# Skematik_Grader-GPS_-_v1.net
KiCad netlist of a schematic drawn in Altium Designer
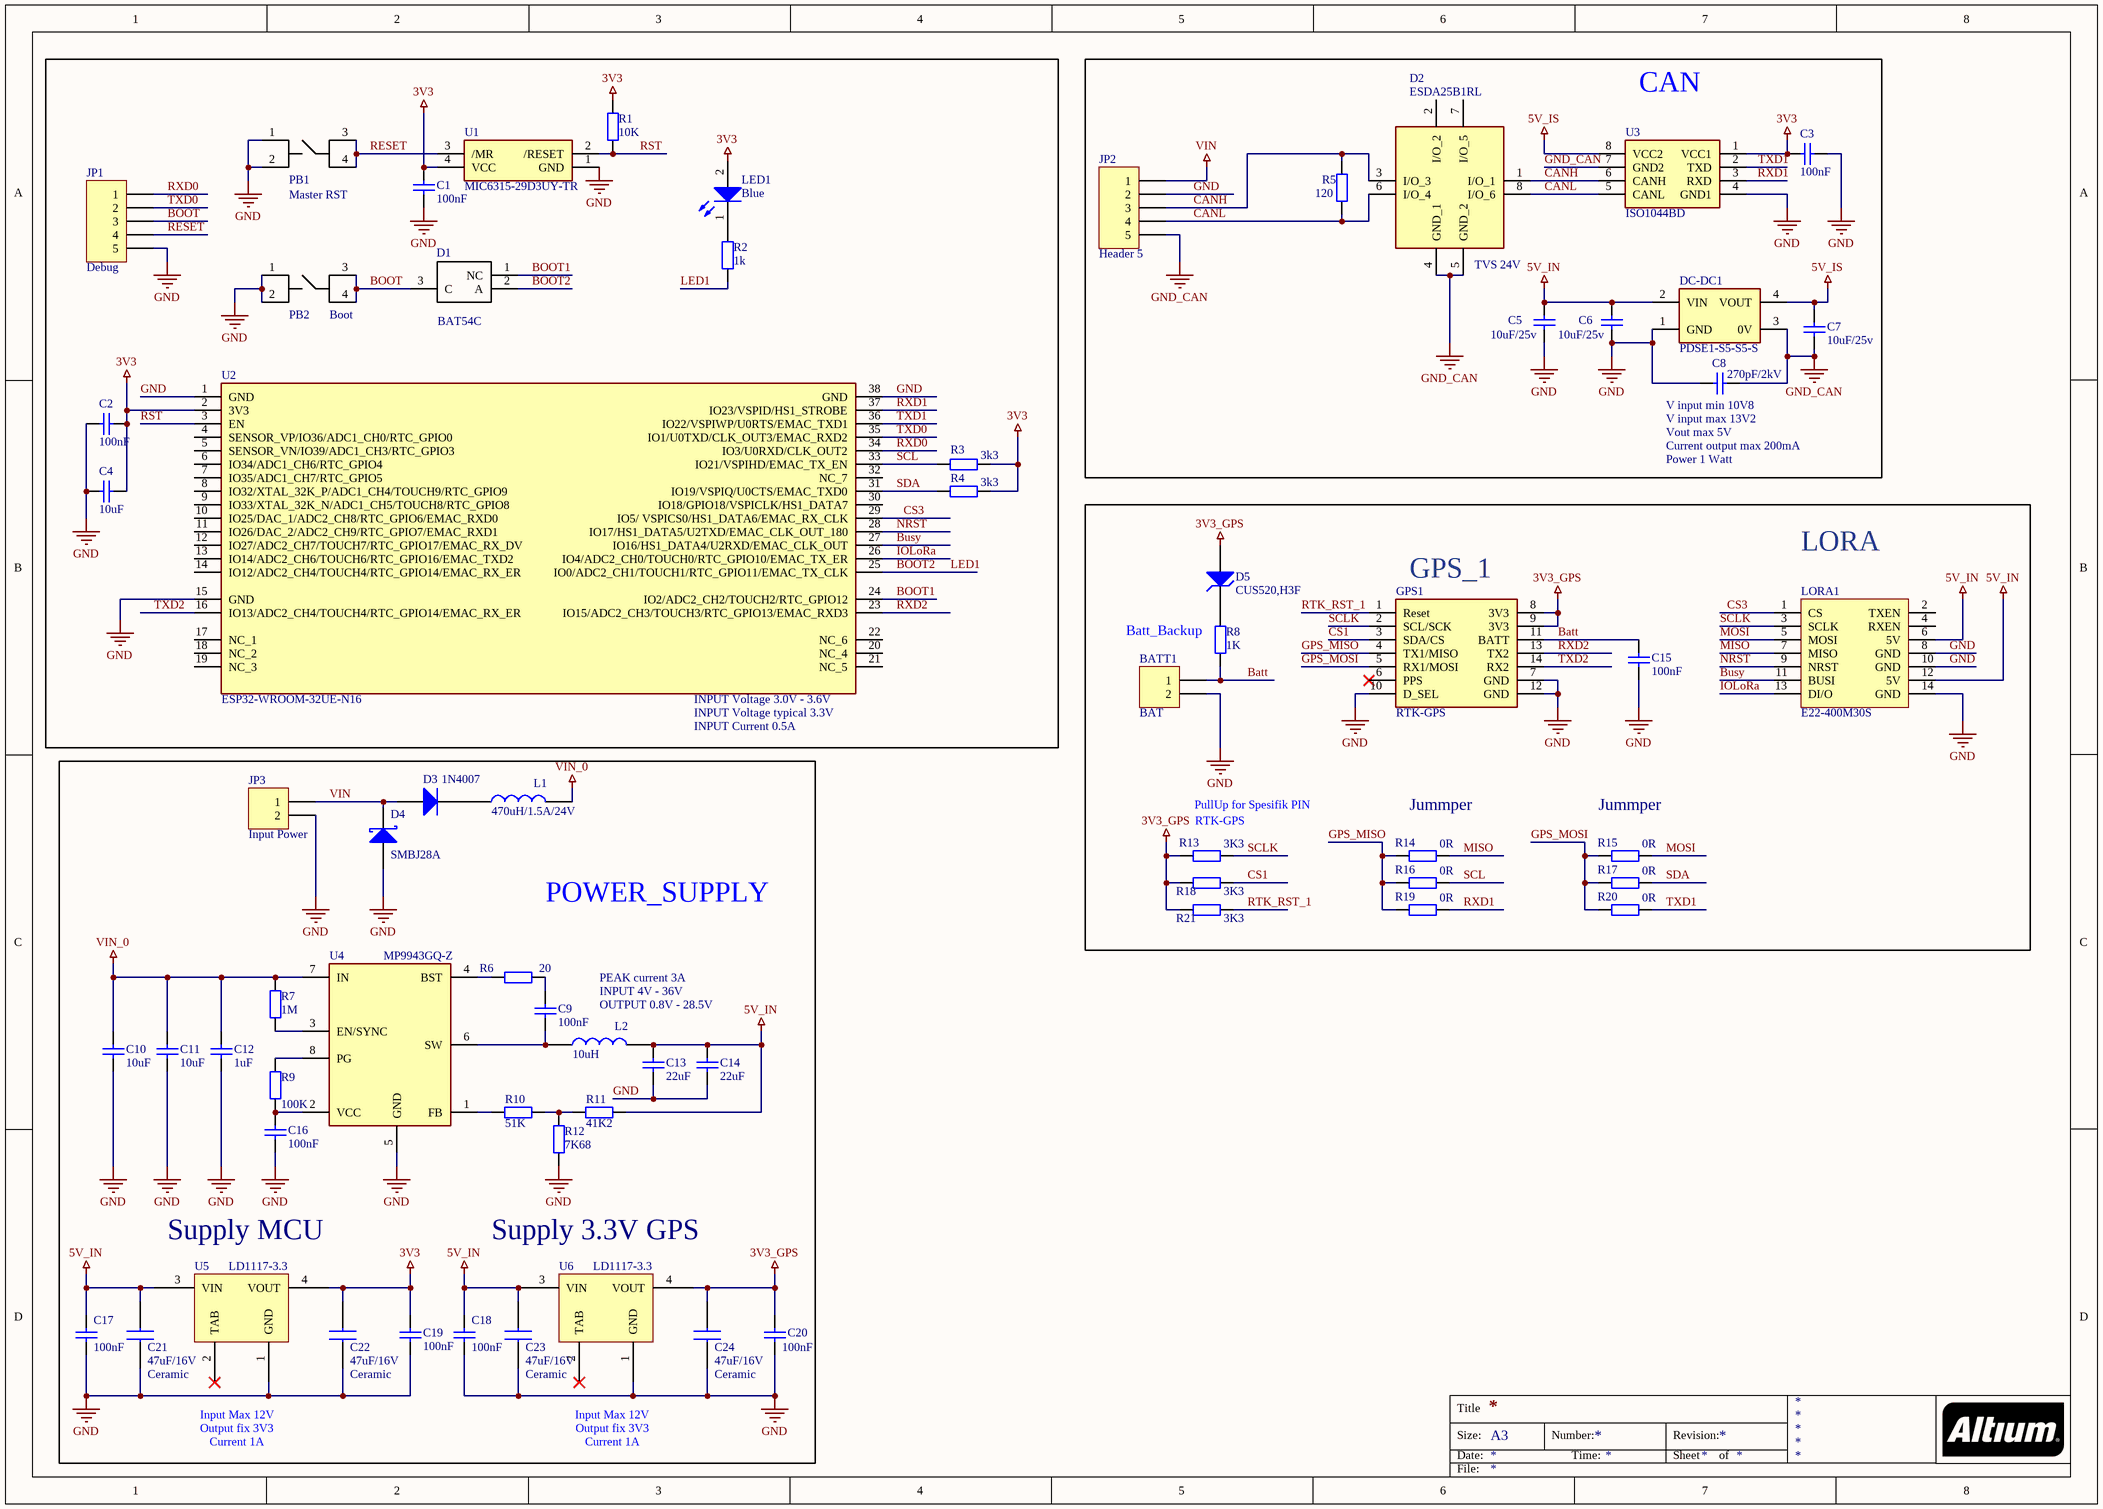
[diagram p0: Skematik_Grader-GPS - v1.SchDoc]

(export (version "E")
  (design (tool "Eeschema 10.0.6"))
  (components
    (comp (ref "BATT1")
      (value "BAT")
      (footprint "CR1220")
      (description "Header, 2-Pin")
      (fields (field (name "PUBLISHER") "Altium Limited"))
      (libsource (lib "Miscellaneous Connectors") (part "MHDR1X2"))
    )
    (comp (ref "C1")
      (value "100nF")
      (footprint "CAPC2012X135N")
      (description "Capacitor")
      (fields (field (name "PUBLISHER") "Altium Limited"))
      (libsource (lib "Miscellaneous Devices") (part "Cap"))
    )
    (comp (ref "C2")
      (value "100nF")
      (footprint "CAPC2012X135N")
      (description "Capacitor")
      (fields (field (name "PUBLISHER") "Altium Limited"))
      (libsource (lib "Miscellaneous Devices") (part "Cap"))
    )
    (comp (ref "C3")
      (value "100nF")
      (footprint "CAPC2012X135N")
      (description "Capacitor")
      (fields (field (name "PUBLISHER") "Altium Limited"))
      (libsource (lib "Miscellaneous Devices") (part "Cap"))
    )
    (comp (ref "C4")
      (value "10uF")
      (footprint "CAPC3216X100N")
      (description "Capacitor")
      (fields (field (name "PUBLISHER") "Altium Limited"))
      (libsource (lib "Miscellaneous Devices") (part "Cap"))
    )
    (comp (ref "C5")
      (value "10uF/25v")
      (footprint "CAPC3216X180N")
      (description "Capacitor")
      (fields (field (name "Comment") "10uF") (field (name "PUBLISHER") "Altium Limited"))
      (libsource (lib "Miscellaneous Devices") (part "Cap"))
    )
    (comp (ref "C6")
      (value "10uF/25v")
      (footprint "CAPC3216X180N")
      (description "Capacitor")
      (fields (field (name "Comment") "10uF") (field (name "PUBLISHER") "Altium Limited"))
      (libsource (lib "Miscellaneous Devices") (part "Cap"))
    )
    (comp (ref "C7")
      (value "10uF/25v")
      (footprint "CAPC3216X100N")
      (description "Capacitor")
      (fields (field (name "Comment") "2.2uF/25V") (field (name "PUBLISHER") "Altium Limited"))
      (libsource (lib "Miscellaneous Devices") (part "Cap"))
    )
    (comp (ref "C8")
      (value "270pF/2kV")
      (footprint "CAPC3216X175N")
      (description "Capacitor")
      (fields (field (name "PUBLISHER") "Altium Limited"))
      (libsource (lib "Miscellaneous Devices") (part "Cap"))
    )
    (comp (ref "C9")
      (value "100nF")
      (footprint "CAPC2012X135N")
      (description "Capacitor")
      (fields (field (name "PUBLISHER") "Altium Limited"))
      (libsource (lib "Miscellaneous Devices") (part "Cap"))
    )
    (comp (ref "C10")
      (value "10uF")
      (footprint "CAPC3216X180N")
      (description "Capacitor")
      (fields (field (name "PUBLISHER") "Altium Limited"))
      (libsource (lib "Miscellaneous Devices") (part "Cap"))
    )
    (comp (ref "C11")
      (value "10uF")
      (footprint "CAPC3216X180N")
      (description "Capacitor")
      (fields (field (name "PUBLISHER") "Altium Limited"))
      (libsource (lib "Miscellaneous Devices") (part "Cap"))
    )
    (comp (ref "C12")
      (value "1uF")
      (footprint "CAPC2012X135N")
      (description "Capacitor")
      (fields (field (name "PUBLISHER") "Altium Limited"))
      (libsource (lib "Miscellaneous Devices") (part "Cap"))
    )
    (comp (ref "C13")
      (value "22uF")
      (footprint "CAPC3216X180N")
      (description "Capacitor")
      (fields (field (name "PUBLISHER") "Altium Limited"))
      (libsource (lib "Miscellaneous Devices") (part "Cap"))
    )
    (comp (ref "C14")
      (value "22uF")
      (footprint "CAPC3216X180N")
      (description "Capacitor")
      (fields (field (name "PUBLISHER") "Altium Limited"))
      (libsource (lib "Miscellaneous Devices") (part "Cap"))
    )
    (comp (ref "C15")
      (value "100nF")
      (footprint "CAPC2012X135N")
      (description "Capacitor")
      (fields (field (name "PUBLISHER") "Altium Limited"))
      (libsource (lib "Miscellaneous Devices") (part "Cap"))
    )
    (comp (ref "C16")
      (value "100nF")
      (footprint "CAPC2012X135N")
      (description "Capacitor")
      (fields (field (name "PUBLISHER") "Altium Limited"))
      (libsource (lib "Miscellaneous Devices") (part "Cap"))
    )
    (comp (ref "C17")
      (value "100nF")
      (footprint "CAPC2012X135N")
      (description "Capacitor")
      (fields (field (name "PUBLISHER") "Altium Limited"))
      (libsource (lib "Miscellaneous Devices") (part "Cap"))
    )
    (comp (ref "C18")
      (value "100nF")
      (footprint "CAPC2012X135N")
      (description "Capacitor")
      (fields (field (name "PUBLISHER") "Altium Limited"))
      (libsource (lib "Miscellaneous Devices") (part "Cap"))
    )
    (comp (ref "C19")
      (value "100nF")
      (footprint "CAPC2012X135N")
      (description "Capacitor")
      (fields (field (name "PUBLISHER") "Altium Limited"))
      (libsource (lib "Miscellaneous Devices") (part "Cap"))
    )
    (comp (ref "C20")
      (value "100nF")
      (footprint "CAPC2012X135N")
      (description "Capacitor")
      (fields (field (name "PUBLISHER") "Altium Limited"))
      (libsource (lib "Miscellaneous Devices") (part "Cap"))
    )
    (comp (ref "C21")
      (value "47uF/16V")
      (footprint "CAPC3225X220N")
      (description "Capacitor")
      (fields
        (field (name "MANUFACTURER_PART_NUMBER") "KCM55WC71E107MH13L")
        (field (name "MOUSER PART NUMBER") "81-KCM55WC71E107MH13")
        (field (name "TYPE") "Ceramic")
      )
      (libsource (lib "*") (part "KCM55WC71E107MH13L"))
    )
    (comp (ref "C22")
      (value "47uF/16V")
      (footprint "CAPC3225X220N")
      (description "Capacitor")
      (fields
        (field (name "MANUFACTURER_PART_NUMBER") "KCM55WC71E107MH13L")
        (field (name "MOUSER PART NUMBER") "81-KCM55WC71E107MH13")
        (field (name "TYPE") "Ceramic")
      )
      (libsource (lib "*") (part "KCM55WC71E107MH13L"))
    )
    (comp (ref "C23")
      (value "47uF/16V")
      (footprint "CAPC3225X220N")
      (description "Capacitor")
      (fields
        (field (name "MANUFACTURER_PART_NUMBER") "KCM55WC71E107MH13L")
        (field (name "MOUSER PART NUMBER") "81-KCM55WC71E107MH13")
        (field (name "TYPE") "Ceramic")
      )
      (libsource (lib "*") (part "KCM55WC71E107MH13L"))
    )
    (comp (ref "C24")
      (value "47uF/16V")
      (footprint "CAPC3225X220N")
      (description "Capacitor")
      (fields
        (field (name "MANUFACTURER_PART_NUMBER") "KCM55WC71E107MH13L")
        (field (name "MOUSER PART NUMBER") "81-KCM55WC71E107MH13")
        (field (name "TYPE") "Ceramic")
      )
      (libsource (lib "*") (part "KCM55WC71E107MH13L"))
    )
    (comp (ref "D1") (value "BAT54C") (footprint "SC59-3") (libsource (lib "Sigit") (part "RB420")))
    (comp (ref "D2")
      (value "ESDA25B1RL")
      (footprint "SOIC127P600X175-8AN")
      (description "TVS DIODA")
      (fields (field (name "MOUSER PART NUMBER") "511-ESDA25B1-TR"))
      (libsource (lib "bayu") (part "ESDA25B1RL"))
    )
    (comp (ref "D3")
      (value "1N4007")
      (footprint "DO-214AC")
      (description "1 Amp General Purpose Rectifier")
      (fields (field (name "PUBLISHER") "Altium Limited"))
      (libsource (lib "Miscellaneous Devices") (part "Diode 1N4001"))
    )
    (comp (ref "D4")
      (value "SMBJ28A")
      (footprint "PBL - SMD Packages:DO-214AA")
      (description "Schottky Diode")
      (fields (field (name "PUBLISHER") "Altium Limited"))
      (libsource (lib "Miscellaneous Devices") (part "D Schottky"))
    )
    (comp (ref "D5")
      (value "CUS520,H3F")
      (footprint "SOD323")
      (description "Zener Diode")
      (fields (field (name "PUBLISHER") "Altium Limited"))
      (libsource (lib "Miscellaneous Devices") (part "D Zener"))
    )
    (comp (ref "DC-DC1")
      (value "PDSE1-S5-S5-S")
      (footprint "DC-DC")
      (description "DC-DC 24 to 12 \r\nPDSE1-S24-S12-S")
      (libsource (lib "rapp") (part "PDSE1-S24-S12-S"))
    )
    (comp (ref "GPS1")
      (value "RTK-GPS")
      (footprint "ZED-F9P")
      (description "GPS Sensor")
      (libsource (lib "rapp") (part "ZED-F9P"))
    )
    (comp (ref "JP1")
      (value "Debug")
      (footprint "HDR1X5")
      (description "Header, 5-Pin")
      (fields (field (name "PUBLISHER") "Altium Limited"))
      (libsource (lib "Miscellaneous Connectors") (part "Header 5"))
    )
    (comp (ref "JP2")
      (value "Header 5")
      (footprint "Term_Block - 5P")
      (description "Header, 5-Pin")
      (fields (field (name "PUBLISHER") "Altium Limited"))
      (libsource (lib "Miscellaneous Connectors") (part "Header 5"))
    )
    (comp (ref "JP3")
      (value "Input Power")
      (footprint "HDR1X2")
      (description "Header, 2-Pin")
      (fields (field (name "PUBLISHER") "Altium Limited"))
      (libsource (lib "Miscellaneous Connectors") (part "Header 2"))
    )
    (comp (ref "L1")
      (value "470uH/1.5A/24V")
      (footprint "INDP9630X28N")
      (description "Inductor")
      (fields
        (field (name "MANUFACTURER_PART_NUMBER") "MPL-AL5050-100")
        (field (name "MOUSER PART NUMBER") "946-MPL-AL5050-100")
      )
      (libsource (lib "*") (part "MPL-AL5050-100"))
    )
    (comp (ref "L2")
      (value "10uH")
      (footprint "IND_5.4x5.3")
      (description "Inductor")
      (fields
        (field (name "MANUFACTURER_PART_NUMBER") "MPL-AL5050-100")
        (field (name "MOUSER PART NUMBER") "946-MPL-AL5050-100")
      )
      (libsource (lib "*") (part "MPL-AL5050-100"))
    )
    (comp (ref "LED1")
      (value "Blue")
      (footprint "LED-0805-A")
      (description "Typical Blue GaAs LED")
      (fields (field (name "PUBLISHER") "Altium Limited"))
      (libsource (lib "Miscellaneous Devices") (part "LED1"))
    )
    (comp (ref "LORA1")
      (value "E22-400M30S")
      (footprint "22s-V3")
      (description "Lora 22S / Lora 30S")
      (libsource (lib "rapp") (part "Lora"))
    )
    (comp (ref "PB1")
      (value "Master RST")
      (footprint "PushButton1688")
      (libsource (lib "Sigit") (part "PB_SW_1"))
    )
    (comp (ref "PB2") (value "Boot") (footprint "PushButton1688") (libsource (lib "Sigit") (part "PB_SW_1")))
    (comp (ref "R1")
      (value "10K")
      (footprint "RESC2012X70N")
      (description "Resistor")
      (fields (field (name "PUBLISHER") "Altium Limited"))
      (libsource (lib "Miscellaneous Devices") (part "Res2"))
    )
    (comp (ref "R2")
      (value "1k")
      (footprint "RESC2012X70N")
      (description "Resistor")
      (fields (field (name "PUBLISHER") "Altium Limited"))
      (libsource (lib "Miscellaneous Devices") (part "Res2"))
    )
    (comp (ref "R3")
      (value "3k3")
      (footprint "RESC2012X70N")
      (description "Resistor")
      (fields (field (name "PUBLISHER") "Altium Limited"))
      (libsource (lib "Miscellaneous Devices") (part "Res2"))
    )
    (comp (ref "R4")
      (value "3k3")
      (footprint "RESC2012X70N")
      (description "Resistor")
      (fields (field (name "PUBLISHER") "Altium Limited"))
      (libsource (lib "Miscellaneous Devices") (part "Res2"))
    )
    (comp (ref "R5")
      (value "120")
      (footprint "RESC2012X70N")
      (description "Resistor")
      (fields (field (name "PUBLISHER") "Altium Limited"))
      (libsource (lib "") (part "Res2_1"))
    )
    (comp (ref "R6")
      (value "20")
      (footprint "RESC2012X70N")
      (description "Resistor")
      (fields (field (name "PUBLISHER") "Altium Limited"))
      (libsource (lib "") (part "Res2_1"))
    )
    (comp (ref "R7")
      (value "1M")
      (footprint "RESC2012X70N")
      (description "Resistor")
      (fields (field (name "PUBLISHER") "Altium Limited"))
      (libsource (lib "") (part "Res2_2"))
    )
    (comp (ref "R8")
      (value "1K")
      (footprint "RESC2012X70N")
      (description "Resistor")
      (fields (field (name "PUBLISHER") "Altium Limited"))
      (libsource (lib "") (part "Res2_3"))
    )
    (comp (ref "R9")
      (value "100K")
      (footprint "RESC2012X70N")
      (description "Resistor")
      (fields (field (name "PUBLISHER") "Altium Limited"))
      (libsource (lib "") (part "Res2_2"))
    )
    (comp (ref "R10")
      (value "51K")
      (footprint "RESC2012X70N")
      (description "Resistor")
      (fields (field (name "PUBLISHER") "Altium Limited"))
      (libsource (lib "") (part "Res2_1"))
    )
    (comp (ref "R11")
      (value "41K2")
      (footprint "RESC2012X70N")
      (description "Resistor")
      (fields (field (name "PUBLISHER") "Altium Limited"))
      (libsource (lib "") (part "Res2_1"))
    )
    (comp (ref "R12")
      (value "7K68")
      (footprint "RESC2012X70N")
      (description "Resistor")
      (fields (field (name "PUBLISHER") "Altium Limited"))
      (libsource (lib "Miscellaneous Devices") (part "Res2"))
    )
    (comp (ref "R13")
      (value "3K3")
      (footprint "RESC2012X70N")
      (description "Resistor")
      (fields (field (name "PUBLISHER") "Altium Limited"))
      (libsource (lib "") (part "Res2_2"))
    )
    (comp (ref "R14")
      (value "0R")
      (footprint "RESC2012X70N")
      (description "Resistor")
      (fields (field (name "PUBLISHER") "Altium Limited"))
      (libsource (lib "") (part "Res2_2"))
    )
    (comp (ref "R15")
      (value "0R")
      (footprint "RESC2012X70N")
      (description "Resistor")
      (fields (field (name "PUBLISHER") "Altium Limited"))
      (libsource (lib "") (part "Res2_2"))
    )
    (comp (ref "R16")
      (value "0R")
      (footprint "RESC2012X70N")
      (description "Resistor")
      (fields (field (name "PUBLISHER") "Altium Limited"))
      (libsource (lib "") (part "Res2_2"))
    )
    (comp (ref "R17")
      (value "0R")
      (footprint "RESC2012X70N")
      (description "Resistor")
      (fields (field (name "PUBLISHER") "Altium Limited"))
      (libsource (lib "") (part "Res2_2"))
    )
    (comp (ref "R18")
      (value "3K3")
      (footprint "RESC2012X70N")
      (description "Resistor")
      (fields (field (name "PUBLISHER") "Altium Limited"))
      (libsource (lib "Miscellaneous Devices") (part "Res2"))
    )
    (comp (ref "R19")
      (value "0R")
      (footprint "RESC2012X70N")
      (description "Resistor")
      (fields (field (name "PUBLISHER") "Altium Limited"))
      (libsource (lib "") (part "Res2_2"))
    )
    (comp (ref "R20")
      (value "0R")
      (footprint "RESC2012X70N")
      (description "Resistor")
      (fields (field (name "PUBLISHER") "Altium Limited"))
      (libsource (lib "") (part "Res2_2"))
    )
    (comp (ref "R21")
      (value "3K3")
      (footprint "RESC2012X70N")
      (description "Resistor")
      (fields (field (name "PUBLISHER") "Altium Limited"))
      (libsource (lib "Miscellaneous Devices") (part "Res2"))
    )
    (comp (ref "U1")
      (value "MIC6315-29D3UY-TR")
      (footprint "MIC631529D3UYTR")
      (description "Integrated Circuit")
      (fields (field (name "MOUSER PART NUMBER") "998-MIC6315-29D3UYTR"))
      (libsource (lib "*") (part "MIC6315-29D3UY-TR"))
    )
    (comp (ref "U2")
      (value "ESP32-WROOM-32UE-N16")
      (footprint "ESP32WROOM32UEN16")
      (libsource (lib "rapp") (part "ESP32-WROOM-32UE-N16A"))
    )
    (comp (ref "U3")
      (value "ISO1044BD")
      (footprint "SOIC127P600X175-8AN")
      (description "Integrated Circuit")
      (fields (field (name "MOUSER PART NUMBER") "595-ISO1044BD"))
      (libsource (lib "*") (part "ISO1044BD"))
    )
    (comp (ref "U4")
      (value "MP9943GQ-Z")
      (footprint "MP9943GQz-smd")
      (description "Integrated Circuit")
      (fields (field (name "MOUSER PART NUMBER") "946-MP9943GQ-Z"))
      (libsource (lib "bayu") (part "MP9943GQ-Z"))
    )
    (comp (ref "U5")
      (value "LD1117-3.3")
      (footprint "PBL - SMD Packages:TO-252")
      (description "AP2114D-3.3TRG1, 3.3V LDO Voltage Regulator")
      (libsource (lib "Sigit") (part "LM1117-3.3V"))
    )
    (comp (ref "U6")
      (value "LD1117-3.3")
      (footprint "PBL - SMD Packages:TO-252")
      (description "AP2114D-3.3TRG1, 3.3V LDO Voltage Regulator")
      (libsource (lib "Sigit") (part "LM1117-3.3V"))
    )
  )
  (nets
    (net (code "1") (name "/BOOT") (class "Default")
      (node (ref "D1") (pin "3") (pinfunction "C_3") (pintype "passive"))
      (node (ref "JP1") (pin "3") (pinfunction "3_3") (pintype "passive"))
      (node (ref "PB2") (pin "3") (pinfunction "3_3") (pintype "passive"))
      (node (ref "PB2") (pin "4") (pinfunction "4_4") (pintype "passive"))
    )
    (net (code "2") (name "/BOOT1") (class "Default")
      (node (ref "D1") (pin "1") (pinfunction "NC_1") (pintype "passive"))
      (node (ref "U2") (pin "24") (pinfunction "IO2/ADC2_CH2/TOUCH2/RTC_GPIO12_24") (pintype "passive"))
    )
    (net (code "3") (name "/BOOT2") (class "Default")
      (node (ref "D1") (pin "2") (pinfunction "A_2") (pintype "passive"))
      (node (ref "R2") (pin "2") (pinfunction "2_2") (pintype "passive"))
      (node (ref "U2") (pin "25") (pinfunction "IO0/ADC2_CH1/TOUCH1/RTC_GPIO11/EMAC_TX_CLK_25") (pintype "passive"))
    )
    (net (code "4") (name "/Batt") (class "Default")
      (node (ref "BATT1") (pin "1") (pinfunction "1_1") (pintype "passive"))
      (node (ref "C15") (pin "2") (pinfunction "2_2") (pintype "passive"))
      (node (ref "GPS1") (pin "11") (pinfunction "BATT_11") (pintype "passive"))
      (node (ref "R8") (pin "1") (pinfunction "1_1") (pintype "passive"))
    )
    (net (code "5") (name "/Busy") (class "Default")
      (node (ref "LORA1") (pin "11") (pinfunction "BUSI_11") (pintype "passive"))
      (node (ref "U2") (pin "27") (pinfunction "IO16/HS1_DATA4/U2RXD/EMAC_CLK_OUT_27") (pintype "passive"))
    )
    (net (code "6") (name "/CANH") (class "Default")
      (node (ref "D2") (pin "1") (pinfunction "I/O_1_1") (pintype "passive"))
      (node (ref "D2") (pin "3") (pinfunction "I/O_3_3") (pintype "passive"))
      (node (ref "JP2") (pin "3") (pinfunction "3_3") (pintype "passive"))
      (node (ref "R5") (pin "1") (pinfunction "1_1") (pintype "passive"))
      (node (ref "U3") (pin "6") (pinfunction "CANH_6") (pintype "passive"))
    )
    (net (code "7") (name "/CANL") (class "Default")
      (node (ref "D2") (pin "6") (pinfunction "I/O_4_6") (pintype "passive"))
      (node (ref "D2") (pin "8") (pinfunction "I/O_6_8") (pintype "passive"))
      (node (ref "JP2") (pin "4") (pinfunction "4_4") (pintype "passive"))
      (node (ref "R5") (pin "2") (pinfunction "2_2") (pintype "passive"))
      (node (ref "U3") (pin "5") (pinfunction "CANL_5") (pintype "passive"))
    )
    (net (code "8") (name "/CS1") (class "Default")
      (node (ref "GPS1") (pin "3") (pinfunction "SDA/CS_3") (pintype "passive"))
      (node (ref "R18") (pin "1") (pinfunction "1_1") (pintype "passive"))
    )
    (net (code "9") (name "/CS3") (class "Default")
      (node (ref "LORA1") (pin "1") (pinfunction "CS_1") (pintype "passive"))
      (node (ref "U2") (pin "29") (pinfunction "IO5/_VSPICS0/HS1_DATA6/EMAC_RX_CLK_29") (pintype "passive"))
    )
    (net (code "10") (name "/GPS_MISO") (class "Default")
      (node (ref "GPS1") (pin "4") (pinfunction "TX1/MISO_4") (pintype "passive"))
      (node (ref "R14") (pin "1") (pinfunction "1_1") (pintype "passive"))
      (node (ref "R16") (pin "1") (pinfunction "1_1") (pintype "passive"))
      (node (ref "R19") (pin "1") (pinfunction "1_1") (pintype "passive"))
    )
    (net (code "11") (name "/GPS_MOSI") (class "Default")
      (node (ref "GPS1") (pin "5") (pinfunction "RX1/MOSI_5") (pintype "passive"))
      (node (ref "R15") (pin "1") (pinfunction "1_1") (pintype "passive"))
      (node (ref "R17") (pin "1") (pinfunction "1_1") (pintype "passive"))
      (node (ref "R20") (pin "1") (pinfunction "1_1") (pintype "passive"))
    )
    (net (code "12") (name "/IOLoRa") (class "Default")
      (node (ref "LORA1") (pin "13") (pinfunction "DI/O_13") (pintype "passive"))
      (node (ref "U2") (pin "26") (pinfunction "IO4/ADC2_CH0/TOUCH0/RTC_GPIO10/EMAC_TX_ER_26") (pintype "passive"))
    )
    (net (code "13") (name "/MISO") (class "Default")
      (node (ref "LORA1") (pin "7") (pinfunction "MISO_7") (pintype "passive"))
      (node (ref "R14") (pin "2") (pinfunction "2_2") (pintype "passive"))
    )
    (net (code "14") (name "/MOSI") (class "Default")
      (node (ref "LORA1") (pin "5") (pinfunction "MOSI_5") (pintype "passive"))
      (node (ref "R15") (pin "2") (pinfunction "2_2") (pintype "passive"))
    )
    (net (code "15") (name "/NRST") (class "Default")
      (node (ref "LORA1") (pin "9") (pinfunction "NRST_9") (pintype "passive"))
      (node (ref "U2") (pin "28") (pinfunction "IO17/HS1_DATA5/U2TXD/EMAC_CLK_OUT_180_28") (pintype "passive"))
    )
    (net (code "16") (name "/RESET") (class "Default")
      (node (ref "JP1") (pin "4") (pinfunction "4_4") (pintype "passive"))
      (node (ref "PB1") (pin "3") (pinfunction "3_3") (pintype "passive"))
      (node (ref "PB1") (pin "4") (pinfunction "4_4") (pintype "passive"))
      (node (ref "U1") (pin "3") (pinfunction "/MR_3") (pintype "passive"))
    )
    (net (code "17") (name "/RST") (class "Default")
      (node (ref "R1") (pin "2") (pinfunction "2_2") (pintype "passive"))
      (node (ref "U1") (pin "2") (pinfunction "/RESET_2") (pintype "passive"))
      (node (ref "U2") (pin "3") (pinfunction "EN_3") (pintype "passive"))
    )
    (net (code "18") (name "/RTK_RST_1") (class "Default")
      (node (ref "GPS1") (pin "1") (pinfunction "Reset_1") (pintype "passive"))
      (node (ref "R21") (pin "1") (pinfunction "1_1") (pintype "passive"))
    )
    (net (code "19") (name "/RXD0") (class "Default")
      (node (ref "JP1") (pin "1") (pinfunction "1_1") (pintype "passive"))
      (node (ref "U2") (pin "34") (pinfunction "IO3/U0RXD/CLK_OUT2_34") (pintype "passive"))
    )
    (net (code "20") (name "/RXD1") (class "Default")
      (node (ref "R19") (pin "2") (pinfunction "2_2") (pintype "passive"))
      (node (ref "U2") (pin "37") (pinfunction "IO23/VSPID/HS1_STROBE_37") (pintype "passive"))
      (node (ref "U3") (pin "3") (pinfunction "RXD_3") (pintype "passive"))
    )
    (net (code "21") (name "/RXD2") (class "Default")
      (node (ref "GPS1") (pin "13") (pinfunction "TX2_13") (pintype "passive"))
      (node (ref "U2") (pin "23") (pinfunction "IO15/ADC2_CH3/TOUCH3/RTC_GPIO13/EMAC_RXD3_23") (pintype "passive"))
    )
    (net (code "22") (name "/SCL") (class "Default")
      (node (ref "R16") (pin "2") (pinfunction "2_2") (pintype "passive"))
      (node (ref "R3") (pin "2") (pinfunction "2_2") (pintype "passive"))
      (node (ref "U2") (pin "33") (pinfunction "IO21/VSPIHD/EMAC_TX_EN_33") (pintype "passive"))
    )
    (net (code "23") (name "/SCLK") (class "Default")
      (node (ref "GPS1") (pin "2") (pinfunction "SCL/SCK_2") (pintype "passive"))
      (node (ref "LORA1") (pin "3") (pinfunction "SCLK_3") (pintype "passive"))
      (node (ref "R13") (pin "2") (pinfunction "2_2") (pintype "passive"))
    )
    (net (code "24") (name "/SDA") (class "Default")
      (node (ref "R17") (pin "2") (pinfunction "2_2") (pintype "passive"))
      (node (ref "R4") (pin "2") (pinfunction "2_2") (pintype "passive"))
      (node (ref "U2") (pin "31") (pinfunction "IO19/VSPIQ/U0CTS/EMAC_TXD0_31") (pintype "passive"))
    )
    (net (code "25") (name "/TXD0") (class "Default")
      (node (ref "JP1") (pin "2") (pinfunction "2_2") (pintype "passive"))
      (node (ref "U2") (pin "35") (pinfunction "IO1/U0TXD/CLK_OUT3/EMAC_RXD2_35") (pintype "passive"))
    )
    (net (code "26") (name "/TXD1") (class "Default")
      (node (ref "R20") (pin "2") (pinfunction "2_2") (pintype "passive"))
      (node (ref "U2") (pin "36") (pinfunction "IO22/VSPIWP/U0RTS/EMAC_TXD1_36") (pintype "passive"))
      (node (ref "U3") (pin "2") (pinfunction "TXD_2") (pintype "passive"))
    )
    (net (code "27") (name "/TXD2") (class "Default")
      (node (ref "GPS1") (pin "14") (pinfunction "RX2_14") (pintype "passive"))
      (node (ref "U2") (pin "16") (pinfunction "IO13/ADC2_CH4/TOUCH4/RTC_GPIO14/EMAC_RX_ER_16") (pintype "passive"))
    )
    (net (code "28") (name "3V3") (class "Default")
      (node (ref "C1") (pin "1") (pinfunction "1_1") (pintype "passive"))
      (node (ref "C19") (pin "2") (pinfunction "2_2") (pintype "passive"))
      (node (ref "C2") (pin "2") (pinfunction "2_2") (pintype "passive"))
      (node (ref "C22") (pin "1") (pinfunction "1_1") (pintype "passive"))
      (node (ref "C3") (pin "1") (pinfunction "1_1") (pintype "passive"))
      (node (ref "C4") (pin "2") (pinfunction "2_2") (pintype "passive"))
      (node (ref "LED1") (pin "2") (pinfunction "A_2") (pintype "passive"))
      (node (ref "R1") (pin "1") (pinfunction "1_1") (pintype "passive"))
      (node (ref "R3") (pin "1") (pinfunction "1_1") (pintype "passive"))
      (node (ref "R4") (pin "1") (pinfunction "1_1") (pintype "passive"))
      (node (ref "U1") (pin "4") (pinfunction "VCC_4") (pintype "passive"))
      (node (ref "U2") (pin "2") (pinfunction "3V3_2") (pintype "passive"))
      (node (ref "U3") (pin "1") (pinfunction "VCC1_1") (pintype "passive"))
      (node (ref "U5") (pin "4") (pinfunction "VOUT_4") (pintype "passive"))
    )
    (net (code "29") (name "3V3_GPS") (class "Default")
      (node (ref "C20") (pin "2") (pinfunction "2_2") (pintype "passive"))
      (node (ref "C24") (pin "1") (pinfunction "1_1") (pintype "passive"))
      (node (ref "D5") (pin "1") (pinfunction "A_1") (pintype "passive"))
      (node (ref "GPS1") (pin "8") (pinfunction "3V3_8") (pintype "passive"))
      (node (ref "GPS1") (pin "9") (pinfunction "3V3_9") (pintype "passive"))
      (node (ref "R13") (pin "1") (pinfunction "1_1") (pintype "passive"))
      (node (ref "R18") (pin "2") (pinfunction "2_2") (pintype "passive"))
      (node (ref "R21") (pin "2") (pinfunction "2_2") (pintype "passive"))
      (node (ref "U6") (pin "4") (pinfunction "VOUT_4") (pintype "passive"))
    )
    (net (code "30") (name "5V_IN") (class "Default")
      (node (ref "C13") (pin "2") (pinfunction "2_2") (pintype "passive"))
      (node (ref "C14") (pin "2") (pinfunction "2_2") (pintype "passive"))
      (node (ref "C17") (pin "2") (pinfunction "2_2") (pintype "passive"))
      (node (ref "C18") (pin "2") (pinfunction "2_2") (pintype "passive"))
      (node (ref "C21") (pin "1") (pinfunction "1_1") (pintype "passive"))
      (node (ref "C23") (pin "1") (pinfunction "1_1") (pintype "passive"))
      (node (ref "C5") (pin "2") (pinfunction "2_2") (pintype "passive"))
      (node (ref "C6") (pin "2") (pinfunction "2_2") (pintype "passive"))
      (node (ref "DC-DC1") (pin "2") (pinfunction "VIN_2") (pintype "passive"))
      (node (ref "L2") (pin "2") (pinfunction "2_2") (pintype "passive"))
      (node (ref "LORA1") (pin "12") (pinfunction "5V_12") (pintype "passive"))
      (node (ref "LORA1") (pin "6") (pinfunction "5V_6") (pintype "passive"))
      (node (ref "R11") (pin "1") (pinfunction "1_1") (pintype "passive"))
      (node (ref "U5") (pin "3") (pinfunction "VIN_3") (pintype "passive"))
      (node (ref "U6") (pin "3") (pinfunction "VIN_3") (pintype "passive"))
    )
    (net (code "31") (name "5V_IS") (class "Default")
      (node (ref "C7") (pin "1") (pinfunction "1_1") (pintype "passive"))
      (node (ref "DC-DC1") (pin "4") (pinfunction "VOUT_4") (pintype "passive"))
      (node (ref "U3") (pin "8") (pinfunction "VCC2_8") (pintype "passive"))
    )
    (net (code "32") (name "GND") (class "Default")
      (node (ref "BATT1") (pin "2") (pinfunction "2_2") (pintype "passive"))
      (node (ref "C1") (pin "2") (pinfunction "2_2") (pintype "passive"))
      (node (ref "C10") (pin "1") (pinfunction "1_1") (pintype "passive"))
      (node (ref "C11") (pin "1") (pinfunction "1_1") (pintype "passive"))
      (node (ref "C12") (pin "1") (pinfunction "1_1") (pintype "passive"))
      (node (ref "C13") (pin "1") (pinfunction "1_1") (pintype "passive"))
      (node (ref "C14") (pin "1") (pinfunction "1_1") (pintype "passive"))
      (node (ref "C15") (pin "1") (pinfunction "1_1") (pintype "passive"))
      (node (ref "C16") (pin "1") (pinfunction "1_1") (pintype "passive"))
      (node (ref "C17") (pin "1") (pinfunction "1_1") (pintype "passive"))
      (node (ref "C18") (pin "1") (pinfunction "1_1") (pintype "passive"))
      (node (ref "C19") (pin "1") (pinfunction "1_1") (pintype "passive"))
      (node (ref "C2") (pin "1") (pinfunction "1_1") (pintype "passive"))
      (node (ref "C20") (pin "1") (pinfunction "1_1") (pintype "passive"))
      (node (ref "C21") (pin "2") (pinfunction "2_2") (pintype "passive"))
      (node (ref "C22") (pin "2") (pinfunction "2_2") (pintype "passive"))
      (node (ref "C23") (pin "2") (pinfunction "2_2") (pintype "passive"))
      (node (ref "C24") (pin "2") (pinfunction "2_2") (pintype "passive"))
      (node (ref "C3") (pin "2") (pinfunction "2_2") (pintype "passive"))
      (node (ref "C4") (pin "1") (pinfunction "1_1") (pintype "passive"))
      (node (ref "C5") (pin "1") (pinfunction "1_1") (pintype "passive"))
      (node (ref "C6") (pin "1") (pinfunction "1_1") (pintype "passive"))
      (node (ref "C8") (pin "1") (pinfunction "1_1") (pintype "passive"))
      (node (ref "D4") (pin "1") (pinfunction "A_1") (pintype "passive"))
      (node (ref "DC-DC1") (pin "1") (pinfunction "GND_1") (pintype "passive"))
      (node (ref "GPS1") (pin "10") (pinfunction "D_SEL_10") (pintype "passive"))
      (node (ref "GPS1") (pin "12") (pinfunction "GND_12") (pintype "passive"))
      (node (ref "GPS1") (pin "7") (pinfunction "GND_7") (pintype "passive"))
      (node (ref "JP1") (pin "5") (pinfunction "5_5") (pintype "passive"))
      (node (ref "JP2") (pin "2") (pinfunction "2_2") (pintype "passive"))
      (node (ref "JP3") (pin "2") (pinfunction "2_2") (pintype "passive"))
      (node (ref "LORA1") (pin "10") (pinfunction "GND_10") (pintype "passive"))
      (node (ref "LORA1") (pin "14") (pinfunction "GND_14") (pintype "passive"))
      (node (ref "LORA1") (pin "8") (pinfunction "GND_8") (pintype "passive"))
      (node (ref "PB1") (pin "1") (pinfunction "1_1") (pintype "passive"))
      (node (ref "PB1") (pin "2") (pinfunction "2_2") (pintype "passive"))
      (node (ref "PB2") (pin "1") (pinfunction "1_1") (pintype "passive"))
      (node (ref "PB2") (pin "2") (pinfunction "2_2") (pintype "passive"))
      (node (ref "R12") (pin "2") (pinfunction "2_2") (pintype "passive"))
      (node (ref "U1") (pin "1") (pinfunction "GND_1") (pintype "passive"))
      (node (ref "U2") (pin "1") (pinfunction "GND_1") (pintype "passive"))
      (node (ref "U2") (pin "15") (pinfunction "GND_15") (pintype "passive"))
      (node (ref "U2") (pin "38") (pinfunction "GND_38") (pintype "passive"))
      (node (ref "U3") (pin "4") (pinfunction "GND1_4") (pintype "passive"))
      (node (ref "U4") (pin "5") (pinfunction "GND_5") (pintype "passive"))
      (node (ref "U5") (pin "1") (pinfunction "GND_1") (pintype "passive"))
      (node (ref "U6") (pin "1") (pinfunction "GND_1") (pintype "passive"))
    )
    (net (code "33") (name "GND_CAN") (class "Default")
      (node (ref "C7") (pin "2") (pinfunction "2_2") (pintype "passive"))
      (node (ref "C8") (pin "2") (pinfunction "2_2") (pintype "passive"))
      (node (ref "D2") (pin "4") (pinfunction "GND_1_4") (pintype "passive"))
      (node (ref "D2") (pin "5") (pinfunction "GND_2_5") (pintype "passive"))
      (node (ref "DC-DC1") (pin "3") (pinfunction "0V_3") (pintype "passive"))
      (node (ref "JP2") (pin "5") (pinfunction "5_5") (pintype "passive"))
      (node (ref "U3") (pin "7") (pinfunction "GND2_7") (pintype "passive"))
    )
    (net (code "34") (name "Net-(C9-Pad2)") (class "Default")
      (node (ref "C9") (pin "2") (pinfunction "2_2") (pintype "passive"))
      (node (ref "R6") (pin "1") (pinfunction "1_1") (pintype "passive"))
    )
    (net (code "35") (name "Net-(D3-K)") (class "Default")
      (node (ref "D3") (pin "2") (pinfunction "K_2") (pintype "passive"))
      (node (ref "L1") (pin "1") (pinfunction "1_1") (pintype "passive"))
    )
    (net (code "36") (name "Net-(D5-K)") (class "Default")
      (node (ref "D5") (pin "2") (pinfunction "K_2") (pintype "passive"))
      (node (ref "R8") (pin "2") (pinfunction "2_2") (pintype "passive"))
    )
    (net (code "37") (name "Net-(LED1-K)") (class "Default")
      (node (ref "LED1") (pin "1") (pinfunction "K_1") (pintype "passive"))
      (node (ref "R2") (pin "1") (pinfunction "1_1") (pintype "passive"))
    )
    (net (code "38") (name "Net-(R10-Pad1)") (class "Default")
      (node (ref "R10") (pin "1") (pinfunction "1_1") (pintype "passive"))
      (node (ref "R11") (pin "2") (pinfunction "2_2") (pintype "passive"))
      (node (ref "R12") (pin "1") (pinfunction "1_1") (pintype "passive"))
    )
    (net (code "39") (name "Net-(U4-BST)") (class "Default")
      (node (ref "R6") (pin "2") (pinfunction "2_2") (pintype "passive"))
      (node (ref "U4") (pin "4") (pinfunction "BST_4") (pintype "passive"))
    )
    (net (code "40") (name "Net-(U4-EN{slash}SYNC)") (class "Default")
      (node (ref "R7") (pin "1") (pinfunction "1_1") (pintype "passive"))
      (node (ref "U4") (pin "3") (pinfunction "EN/SYNC_3") (pintype "passive"))
    )
    (net (code "41") (name "Net-(U4-FB)") (class "Default")
      (node (ref "R10") (pin "2") (pinfunction "2_2") (pintype "passive"))
      (node (ref "U4") (pin "1") (pinfunction "FB_1") (pintype "passive"))
    )
    (net (code "42") (name "Net-(U4-PG)") (class "Default")
      (node (ref "R9") (pin "2") (pinfunction "2_2") (pintype "passive"))
      (node (ref "U4") (pin "8") (pinfunction "PG_8") (pintype "passive"))
    )
    (net (code "43") (name "Net-(U4-SW)") (class "Default")
      (node (ref "C9") (pin "1") (pinfunction "1_1") (pintype "passive"))
      (node (ref "L2") (pin "1") (pinfunction "1_1") (pintype "passive"))
      (node (ref "U4") (pin "6") (pinfunction "SW_6") (pintype "passive"))
    )
    (net (code "44") (name "Net-(U4-VCC)") (class "Default")
      (node (ref "C16") (pin "2") (pinfunction "2_2") (pintype "passive"))
      (node (ref "R9") (pin "1") (pinfunction "1_1") (pintype "passive"))
      (node (ref "U4") (pin "2") (pinfunction "VCC_2") (pintype "passive"))
    )
    (net (code "45") (name "VIN") (class "Default")
      (node (ref "D3") (pin "1") (pinfunction "A_1") (pintype "passive"))
      (node (ref "D4") (pin "2") (pinfunction "K_2") (pintype "passive"))
      (node (ref "JP2") (pin "1") (pinfunction "1_1") (pintype "passive"))
      (node (ref "JP3") (pin "1") (pinfunction "1_1") (pintype "passive"))
    )
    (net (code "46") (name "VIN_0") (class "Default")
      (node (ref "C10") (pin "2") (pinfunction "2_2") (pintype "passive"))
      (node (ref "C11") (pin "2") (pinfunction "2_2") (pintype "passive"))
      (node (ref "C12") (pin "2") (pinfunction "2_2") (pintype "passive"))
      (node (ref "L1") (pin "2") (pinfunction "2_2") (pintype "passive"))
      (node (ref "R7") (pin "2") (pinfunction "2_2") (pintype "passive"))
      (node (ref "U4") (pin "7") (pinfunction "IN_7") (pintype "passive"))
    )
    (net (code "47") (name "unconnected-(D2-I{slash}O_2-Pad2)") (class "Default")
      (node (ref "D2") (pin "2") (pinfunction "I/O_2_2") (pintype "passive"))
    )
    (net (code "48") (name "unconnected-(D2-I{slash}O_5-Pad7)") (class "Default")
      (node (ref "D2") (pin "7") (pinfunction "I/O_5_7") (pintype "passive"))
    )
    (net (code "49") (name "unconnected-(GPS1-PPS-Pad6)") (class "Default")
      (node (ref "GPS1") (pin "6") (pinfunction "PPS_6") (pintype "passive+no_connect"))
    )
    (net (code "50") (name "unconnected-(LORA1-RXEN-Pad4)") (class "Default")
      (node (ref "LORA1") (pin "4") (pinfunction "RXEN_4") (pintype "passive"))
    )
    (net (code "51") (name "unconnected-(LORA1-TXEN-Pad2)") (class "Default")
      (node (ref "LORA1") (pin "2") (pinfunction "TXEN_2") (pintype "passive"))
    )
    (net (code "52") (name "unconnected-(U2-IO12{slash}ADC2_CH4{slash}TOUCH4{slash}RTC_GPIO14{slash}EMAC_RX_ER-Pad14)") (class "Default")
      (node (ref "U2") (pin "14") (pinfunction "IO12/ADC2_CH4/TOUCH4/RTC_GPIO14/EMAC_RX_ER_14") (pintype "passive"))
    )
    (net (code "53") (name "unconnected-(U2-IO14{slash}ADC2_CH6{slash}TOUCH6{slash}RTC_GPIO16{slash}EMAC_TXD2-Pad13)") (class "Default")
      (node (ref "U2") (pin "13") (pinfunction "IO14/ADC2_CH6/TOUCH6/RTC_GPIO16/EMAC_TXD2_13") (pintype "passive"))
    )
    (net (code "54") (name "unconnected-(U2-IO18{slash}GPIO18{slash}VSPICLK{slash}HS1_DATA7-Pad30)") (class "Default")
      (node (ref "U2") (pin "30") (pinfunction "IO18/GPIO18/VSPICLK/HS1_DATA7_30") (pintype "passive"))
    )
    (net (code "55") (name "unconnected-(U2-IO25{slash}DAC_1{slash}ADC2_CH8{slash}RTC_GPIO6{slash}EMAC_RXD0-Pad10)") (class "Default")
      (node (ref "U2") (pin "10") (pinfunction "IO25/DAC_1/ADC2_CH8/RTC_GPIO6/EMAC_RXD0_10") (pintype "passive"))
    )
    (net (code "56") (name "unconnected-(U2-IO26{slash}DAC_2{slash}ADC2_CH9{slash}RTC_GPIO7{slash}EMAC_RXD1-Pad11)") (class "Default")
      (node (ref "U2") (pin "11") (pinfunction "IO26/DAC_2/ADC2_CH9/RTC_GPIO7/EMAC_RXD1_11") (pintype "passive"))
    )
    (net (code "57") (name "unconnected-(U2-IO27{slash}ADC2_CH7{slash}TOUCH7{slash}RTC_GPIO17{slash}EMAC_RX_DV-Pad12)") (class "Default")
      (node (ref "U2") (pin "12") (pinfunction "IO27/ADC2_CH7/TOUCH7/RTC_GPIO17/EMAC_RX_DV_12") (pintype "passive"))
    )
    (net (code "58") (name "unconnected-(U2-IO32{slash}XTAL_32K_P{slash}ADC1_CH4{slash}TOUCH9{slash}RTC_GPIO9-Pad8)") (class "Default")
      (node (ref "U2") (pin "8") (pinfunction "IO32/XTAL_32K_P/ADC1_CH4/TOUCH9/RTC_GPIO9_8") (pintype "passive"))
    )
    (net (code "59") (name "unconnected-(U2-IO33{slash}XTAL_32K_N{slash}ADC1_CH5{slash}TOUCH8{slash}RTC_GPIO8-Pad9)") (class "Default")
      (node (ref "U2") (pin "9") (pinfunction "IO33/XTAL_32K_N/ADC1_CH5/TOUCH8/RTC_GPIO8_9") (pintype "passive"))
    )
    (net (code "60") (name "unconnected-(U2-IO34{slash}ADC1_CH6{slash}RTC_GPIO4-Pad6)") (class "Default")
      (node (ref "U2") (pin "6") (pinfunction "IO34/ADC1_CH6/RTC_GPIO4_6") (pintype "passive"))
    )
    (net (code "61") (name "unconnected-(U2-IO35{slash}ADC1_CH7{slash}RTC_GPIO5-Pad7)") (class "Default")
      (node (ref "U2") (pin "7") (pinfunction "IO35/ADC1_CH7/RTC_GPIO5_7") (pintype "passive"))
    )
    (net (code "62") (name "unconnected-(U2-NC_1-Pad17)") (class "Default")
      (node (ref "U2") (pin "17") (pinfunction "NC_1_17") (pintype "passive"))
    )
    (net (code "63") (name "unconnected-(U2-NC_2-Pad18)") (class "Default")
      (node (ref "U2") (pin "18") (pinfunction "NC_2_18") (pintype "passive"))
    )
    (net (code "64") (name "unconnected-(U2-NC_3-Pad19)") (class "Default")
      (node (ref "U2") (pin "19") (pinfunction "NC_3_19") (pintype "passive"))
    )
    (net (code "65") (name "unconnected-(U2-NC_4-Pad20)") (class "Default")
      (node (ref "U2") (pin "20") (pinfunction "NC_4_20") (pintype "passive"))
    )
    (net (code "66") (name "unconnected-(U2-NC_5-Pad21)") (class "Default")
      (node (ref "U2") (pin "21") (pinfunction "NC_5_21") (pintype "passive"))
    )
    (net (code "67") (name "unconnected-(U2-NC_6-Pad22)") (class "Default")
      (node (ref "U2") (pin "22") (pinfunction "NC_6_22") (pintype "passive"))
    )
    (net (code "68") (name "unconnected-(U2-NC_7-Pad32)") (class "Default")
      (node (ref "U2") (pin "32") (pinfunction "NC_7_32") (pintype "passive"))
    )
    (net (code "69") (name "unconnected-(U2-SENSOR_VN{slash}IO39{slash}ADC1_CH3{slash}RTC_GPIO3-Pad5)") (class "Default")
      (node (ref "U2") (pin "5") (pinfunction "SENSOR_VN/IO39/ADC1_CH3/RTC_GPIO3_5") (pintype "passive"))
    )
    (net (code "70") (name "unconnected-(U2-SENSOR_VP{slash}IO36{slash}ADC1_CH0{slash}RTC_GPIO0-Pad4)") (class "Default")
      (node (ref "U2") (pin "4") (pinfunction "SENSOR_VP/IO36/ADC1_CH0/RTC_GPIO0_4") (pintype "passive"))
    )
    (net (code "71") (name "unconnected-(U5-TAB-Pad2)") (class "Default")
      (node (ref "U5") (pin "2") (pinfunction "TAB_2") (pintype "passive+no_connect"))
    )
    (net (code "72") (name "unconnected-(U6-TAB-Pad2)") (class "Default")
      (node (ref "U6") (pin "2") (pinfunction "TAB_2") (pintype "passive+no_connect"))
    )
  )
)
